# 485Driver_MAX3462.net
KiCad netlist of a schematic drawn in Altium Designer
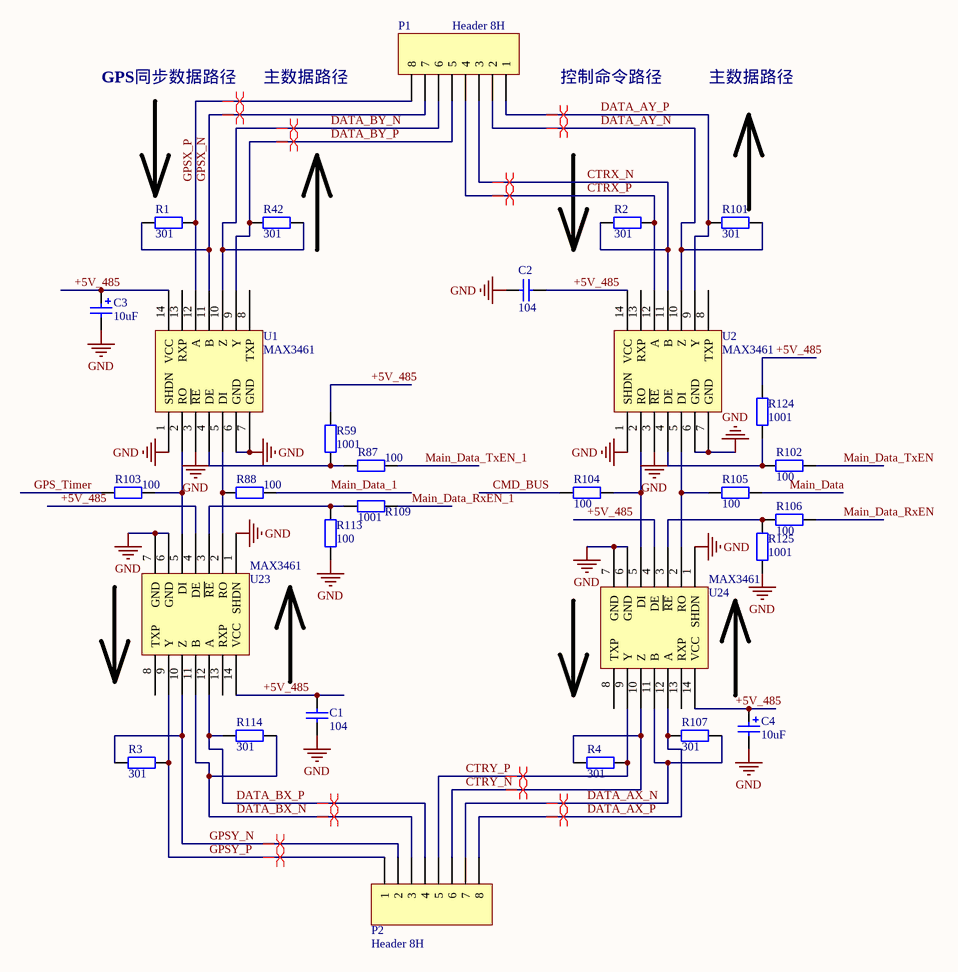
[diagram p0: 485Driver_MAX3462.SchDoc]

(export (version "E")
  (design (tool "Eeschema 10.0.6"))
  (components
    (comp (ref "C1")
      (value "104")
      (footprint "0805C")
      (description "Capacitor")
      (fields (field (name "PUBLISHER") "Altium Limited"))
      (libsource (lib "Miscellaneous Devices") (part "Cap"))
    )
    (comp (ref "C2")
      (value "104")
      (footprint "0805C")
      (description "Capacitor")
      (fields (field (name "PUBLISHER") "Altium Limited"))
      (libsource (lib "Miscellaneous Devices") (part "Cap"))
    )
    (comp (ref "C3")
      (value "10uF")
      (footprint "C68uF")
      (description "Polarized Capacitor (Axial)")
      (fields (field (name "PUBLISHER") "Altium Limited"))
      (libsource (lib "Miscellaneous Devices") (part "Cap Pol2"))
    )
    (comp (ref "C4")
      (value "10uF")
      (footprint "C68uF")
      (description "Polarized Capacitor (Axial)")
      (fields (field (name "PUBLISHER") "Altium Limited"))
      (libsource (lib "Miscellaneous Devices") (part "Cap Pol2"))
    )
    (comp (ref "P1")
      (value "Header 8H")
      (footprint "HDR1X8H")
      (description "Header, 8-Pin, Right Angle")
      (fields (field (name "PUBLISHER") "Altium Limited"))
      (libsource (lib "Miscellaneous Connectors") (part "Header 8H"))
    )
    (comp (ref "P2")
      (value "Header 8H")
      (footprint "HDR1X8H")
      (description "Header, 8-Pin, Right Angle")
      (fields (field (name "PUBLISHER") "Altium Limited"))
      (libsource (lib "") (part "Header 8H_1"))
    )
    (comp (ref "R1")
      (value "301")
      (footprint "0805R")
      (description "Resistor")
      (fields (field (name "PUBLISHER") "Altium Limited"))
      (libsource (lib "Miscellaneous Devices") (part "Res2"))
    )
    (comp (ref "R2")
      (value "301")
      (footprint "0805R")
      (description "Resistor")
      (fields (field (name "PUBLISHER") "Altium Limited"))
      (libsource (lib "Miscellaneous Devices") (part "Res2"))
    )
    (comp (ref "R3")
      (value "301")
      (footprint "0805R")
      (description "Resistor")
      (fields (field (name "PUBLISHER") "Altium Limited"))
      (libsource (lib "Miscellaneous Devices") (part "Res2"))
    )
    (comp (ref "R4")
      (value "301")
      (footprint "0805R")
      (description "Resistor")
      (fields (field (name "PUBLISHER") "Altium Limited"))
      (libsource (lib "Miscellaneous Devices") (part "Res2"))
    )
    (comp (ref "R42")
      (value "301")
      (footprint "0805R")
      (description "Resistor")
      (fields (field (name "PUBLISHER") "Altium Limited"))
      (libsource (lib "Miscellaneous Devices") (part "Res2"))
    )
    (comp (ref "R59")
      (value "1001")
      (footprint "0603")
      (description "Resistor")
      (fields (field (name "PUBLISHER") "Altium Limited"))
      (libsource (lib "") (part "Res2_2"))
    )
    (comp (ref "R87")
      (value "100")
      (footprint "0603")
      (description "Resistor")
      (fields (field (name "PUBLISHER") "Altium Limited"))
      (libsource (lib "Miscellaneous Devices") (part "Res2"))
    )
    (comp (ref "R88")
      (value "100")
      (footprint "0603")
      (description "Resistor")
      (fields (field (name "PUBLISHER") "Altium Limited"))
      (libsource (lib "Miscellaneous Devices") (part "Res2"))
    )
    (comp (ref "R101")
      (value "301")
      (footprint "0805R")
      (description "Resistor")
      (fields (field (name "PUBLISHER") "Altium Limited"))
      (libsource (lib "Miscellaneous Devices") (part "Res2"))
    )
    (comp (ref "R102")
      (value "100")
      (footprint "0603")
      (description "Resistor")
      (fields (field (name "PUBLISHER") "Altium Limited"))
      (libsource (lib "Miscellaneous Devices") (part "Res2"))
    )
    (comp (ref "R103")
      (value "100")
      (footprint "0603")
      (description "Resistor")
      (fields (field (name "PUBLISHER") "Altium Limited"))
      (libsource (lib "Miscellaneous Devices") (part "Res2"))
    )
    (comp (ref "R104")
      (value "100")
      (footprint "0603")
      (description "Resistor")
      (fields (field (name "PUBLISHER") "Altium Limited"))
      (libsource (lib "Miscellaneous Devices") (part "Res2"))
    )
    (comp (ref "R105")
      (value "100")
      (footprint "0603")
      (description "Resistor")
      (fields (field (name "PUBLISHER") "Altium Limited"))
      (libsource (lib "Miscellaneous Devices") (part "Res2"))
    )
    (comp (ref "R106")
      (value "100")
      (footprint "0603")
      (description "Resistor")
      (fields (field (name "PUBLISHER") "Altium Limited"))
      (libsource (lib "Miscellaneous Devices") (part "Res2"))
    )
    (comp (ref "R107")
      (value "301")
      (footprint "0805R")
      (description "Resistor")
      (fields (field (name "PUBLISHER") "Altium Limited"))
      (libsource (lib "Miscellaneous Devices") (part "Res2"))
    )
    (comp (ref "R109")
      (value "1001")
      (footprint "0603")
      (description "Resistor")
      (fields (field (name "PUBLISHER") "Altium Limited"))
      (libsource (lib "") (part "Res2_1"))
    )
    (comp (ref "R113")
      (value "100")
      (footprint "0603")
      (description "Resistor")
      (fields (field (name "PUBLISHER") "Altium Limited"))
      (libsource (lib "") (part "Res2_2"))
    )
    (comp (ref "R114")
      (value "301")
      (footprint "0805R")
      (description "Resistor")
      (fields (field (name "PUBLISHER") "Altium Limited"))
      (libsource (lib "Miscellaneous Devices") (part "Res2"))
    )
    (comp (ref "R124")
      (value "1001")
      (footprint "0603")
      (description "Resistor")
      (fields (field (name "PUBLISHER") "Altium Limited"))
      (libsource (lib "") (part "Res2_2"))
    )
    (comp (ref "R125")
      (value "1001")
      (footprint "0603")
      (description "Resistor")
      (fields (field (name "PUBLISHER") "Altium Limited"))
      (libsource (lib "") (part "Res2_2"))
    )
    (comp (ref "U1") (value "MAX3461") (footprint "SOP14") (libsource (lib "Schlib1") (part "MAX3461")))
    (comp (ref "U2") (value "MAX3461") (footprint "SOP14") (libsource (lib "Schlib1") (part "MAX3461")))
    (comp (ref "U23") (value "MAX3461") (footprint "SOP14") (libsource (lib "") (part "MAX3461_1")))
    (comp (ref "U24") (value "MAX3461") (footprint "SOP14") (libsource (lib "") (part "MAX3461_1")))
  )
  (nets
    (net (code "1") (name "/+5V_485") (class "Default")
      (node (ref "C1") (pin "2") (pinfunction "2_2") (pintype "passive"))
      (node (ref "C2") (pin "2") (pinfunction "2_2") (pintype "passive"))
      (node (ref "C3") (pin "1") (pinfunction "1_1") (pintype "passive"))
      (node (ref "C4") (pin "1") (pinfunction "1_1") (pintype "passive"))
      (node (ref "R124") (pin "1") (pinfunction "1_1") (pintype "passive"))
      (node (ref "R59") (pin "1") (pinfunction "1_1") (pintype "passive"))
      (node (ref "U1") (pin "14") (pinfunction "VCC_14") (pintype "passive"))
      (node (ref "U2") (pin "14") (pinfunction "VCC_14") (pintype "passive"))
      (node (ref "U23") (pin "14") (pinfunction "VCC_14") (pintype "passive"))
      (node (ref "U23") (pin "4") (pinfunction "DE_4") (pintype "passive"))
      (node (ref "U24") (pin "14") (pinfunction "VCC_14") (pintype "passive"))
      (node (ref "U24") (pin "4") (pinfunction "DE_4") (pintype "passive"))
    )
    (net (code "2") (name "/CMD_BUS") (class "Default")
      (node (ref "R104") (pin "2") (pinfunction "2_2") (pintype "passive"))
    )
    (net (code "3") (name "/CTRX_N") (class "Default")
      (node (ref "P1") (pin "3") (pinfunction "3_3") (pintype "passive"))
      (node (ref "R2") (pin "2") (pinfunction "2_2") (pintype "passive"))
      (node (ref "U2") (pin "11") (pinfunction "B_11") (pintype "passive"))
    )
    (net (code "4") (name "/CTRX_P") (class "Default")
      (node (ref "P1") (pin "4") (pinfunction "4_4") (pintype "passive"))
      (node (ref "R2") (pin "1") (pinfunction "1_1") (pintype "passive"))
      (node (ref "U2") (pin "12") (pinfunction "A_12") (pintype "passive"))
    )
    (net (code "5") (name "/CTRY_N") (class "Default")
      (node (ref "P2") (pin "6") (pinfunction "6_6") (pintype "passive"))
      (node (ref "R4") (pin "2") (pinfunction "2_2") (pintype "passive"))
      (node (ref "U24") (pin "10") (pinfunction "Z_10") (pintype "passive"))
    )
    (net (code "6") (name "/CTRY_P") (class "Default")
      (node (ref "P2") (pin "5") (pinfunction "5_5") (pintype "passive"))
      (node (ref "R4") (pin "1") (pinfunction "1_1") (pintype "passive"))
      (node (ref "U24") (pin "9") (pinfunction "Y_9") (pintype "passive"))
    )
    (net (code "7") (name "/DATA_AX_N") (class "Default")
      (node (ref "P2") (pin "7") (pinfunction "7_7") (pintype "passive"))
      (node (ref "R107") (pin "1") (pinfunction "1_1") (pintype "passive"))
      (node (ref "U24") (pin "11") (pinfunction "B_11") (pintype "passive"))
    )
    (net (code "8") (name "/DATA_AX_P") (class "Default")
      (node (ref "P2") (pin "8") (pinfunction "8_8") (pintype "passive"))
      (node (ref "R107") (pin "2") (pinfunction "2_2") (pintype "passive"))
      (node (ref "U24") (pin "12") (pinfunction "A_12") (pintype "passive"))
    )
    (net (code "9") (name "/DATA_AY_N") (class "Default")
      (node (ref "P1") (pin "2") (pinfunction "2_2") (pintype "passive"))
      (node (ref "R101") (pin "1") (pinfunction "1_1") (pintype "passive"))
      (node (ref "U2") (pin "10") (pinfunction "Z_10") (pintype "passive"))
    )
    (net (code "10") (name "/DATA_AY_P") (class "Default")
      (node (ref "P1") (pin "1") (pinfunction "1_1") (pintype "passive"))
      (node (ref "R101") (pin "2") (pinfunction "2_2") (pintype "passive"))
      (node (ref "U2") (pin "9") (pinfunction "Y_9") (pintype "passive"))
    )
    (net (code "11") (name "/DATA_BX_N") (class "Default")
      (node (ref "P2") (pin "3") (pinfunction "3_3") (pintype "passive"))
      (node (ref "R114") (pin "1") (pinfunction "1_1") (pintype "passive"))
      (node (ref "U23") (pin "11") (pinfunction "B_11") (pintype "passive"))
    )
    (net (code "12") (name "/DATA_BX_P") (class "Default")
      (node (ref "P2") (pin "4") (pinfunction "4_4") (pintype "passive"))
      (node (ref "R114") (pin "2") (pinfunction "2_2") (pintype "passive"))
      (node (ref "U23") (pin "12") (pinfunction "A_12") (pintype "passive"))
    )
    (net (code "13") (name "/DATA_BY_N") (class "Default")
      (node (ref "P1") (pin "6") (pinfunction "6_6") (pintype "passive"))
      (node (ref "R42") (pin "1") (pinfunction "1_1") (pintype "passive"))
      (node (ref "U1") (pin "10") (pinfunction "Z_10") (pintype "passive"))
    )
    (net (code "14") (name "/DATA_BY_P") (class "Default")
      (node (ref "P1") (pin "5") (pinfunction "5_5") (pintype "passive"))
      (node (ref "R42") (pin "2") (pinfunction "2_2") (pintype "passive"))
      (node (ref "U1") (pin "9") (pinfunction "Y_9") (pintype "passive"))
    )
    (net (code "15") (name "/GPSX_N") (class "Default")
      (node (ref "P1") (pin "7") (pinfunction "7_7") (pintype "passive"))
      (node (ref "R1") (pin "2") (pinfunction "2_2") (pintype "passive"))
      (node (ref "U1") (pin "11") (pinfunction "B_11") (pintype "passive"))
    )
    (net (code "16") (name "/GPSX_P") (class "Default")
      (node (ref "P1") (pin "8") (pinfunction "8_8") (pintype "passive"))
      (node (ref "R1") (pin "1") (pinfunction "1_1") (pintype "passive"))
      (node (ref "U1") (pin "12") (pinfunction "A_12") (pintype "passive"))
    )
    (net (code "17") (name "/GPSY_N") (class "Default")
      (node (ref "P2") (pin "2") (pinfunction "2_2") (pintype "passive"))
      (node (ref "R3") (pin "2") (pinfunction "2_2") (pintype "passive"))
      (node (ref "U23") (pin "10") (pinfunction "Z_10") (pintype "passive"))
    )
    (net (code "18") (name "/GPSY_P") (class "Default")
      (node (ref "P2") (pin "1") (pinfunction "1_1") (pintype "passive"))
      (node (ref "R3") (pin "1") (pinfunction "1_1") (pintype "passive"))
      (node (ref "U23") (pin "9") (pinfunction "Y_9") (pintype "passive"))
    )
    (net (code "19") (name "/GPS_Timer") (class "Default")
      (node (ref "R103") (pin "2") (pinfunction "2_2") (pintype "passive"))
    )
    (net (code "20") (name "/Main_Data") (class "Default")
      (node (ref "R105") (pin "1") (pinfunction "1_1") (pintype "passive"))
    )
    (net (code "21") (name "/Main_Data_1") (class "Default")
      (node (ref "R88") (pin "1") (pinfunction "1_1") (pintype "passive"))
    )
    (net (code "22") (name "/Main_Data_RxEN") (class "Default")
      (node (ref "R106") (pin "1") (pinfunction "1_1") (pintype "passive"))
    )
    (net (code "23") (name "/Main_Data_RxEN_1") (class "Default")
      (node (ref "R109") (pin "2") (pinfunction "2_2") (pintype "passive"))
    )
    (net (code "24") (name "/Main_Data_TxEN") (class "Default")
      (node (ref "R102") (pin "1") (pinfunction "1_1") (pintype "passive"))
    )
    (net (code "25") (name "/Main_Data_TxEN_1") (class "Default")
      (node (ref "R87") (pin "1") (pinfunction "1_1") (pintype "passive"))
    )
    (net (code "26") (name "GND") (class "Default")
      (node (ref "C1") (pin "1") (pinfunction "1_1") (pintype "passive"))
      (node (ref "C2") (pin "1") (pinfunction "1_1") (pintype "passive"))
      (node (ref "C3") (pin "2") (pinfunction "2_2") (pintype "passive"))
      (node (ref "C4") (pin "2") (pinfunction "2_2") (pintype "passive"))
      (node (ref "R113") (pin "2") (pinfunction "2_2") (pintype "passive"))
      (node (ref "R125") (pin "2") (pinfunction "2_2") (pintype "passive"))
      (node (ref "U1") (pin "1") (pinfunction "SHDN_1") (pintype "passive"))
      (node (ref "U1") (pin "3") (pinfunction "~{RE}_3") (pintype "passive"))
      (node (ref "U1") (pin "6") (pinfunction "GND_6") (pintype "passive"))
      (node (ref "U1") (pin "7") (pinfunction "GND_7") (pintype "passive"))
      (node (ref "U2") (pin "1") (pinfunction "SHDN_1") (pintype "passive"))
      (node (ref "U2") (pin "3") (pinfunction "~{RE}_3") (pintype "passive"))
      (node (ref "U2") (pin "6") (pinfunction "GND_6") (pintype "passive"))
      (node (ref "U2") (pin "7") (pinfunction "GND_7") (pintype "passive"))
      (node (ref "U23") (pin "1") (pinfunction "SHDN_1") (pintype "passive"))
      (node (ref "U23") (pin "6") (pinfunction "GND_6") (pintype "passive"))
      (node (ref "U23") (pin "7") (pinfunction "GND_7") (pintype "passive"))
      (node (ref "U24") (pin "1") (pinfunction "SHDN_1") (pintype "passive"))
      (node (ref "U24") (pin "6") (pinfunction "GND_6") (pintype "passive"))
      (node (ref "U24") (pin "7") (pinfunction "GND_7") (pintype "passive"))
    )
    (net (code "27") (name "Net-(U1-DE)") (class "Default")
      (node (ref "R59") (pin "2") (pinfunction "2_2") (pintype "passive"))
      (node (ref "R87") (pin "2") (pinfunction "2_2") (pintype "passive"))
      (node (ref "U1") (pin "4") (pinfunction "DE_4") (pintype "passive"))
    )
    (net (code "28") (name "Net-(U1-DI)") (class "Default")
      (node (ref "R88") (pin "2") (pinfunction "2_2") (pintype "passive"))
      (node (ref "U1") (pin "5") (pinfunction "DI_5") (pintype "passive"))
      (node (ref "U23") (pin "2") (pinfunction "RO_2") (pintype "passive"))
    )
    (net (code "29") (name "Net-(U1-RO)") (class "Default")
      (node (ref "R103") (pin "1") (pinfunction "1_1") (pintype "passive"))
      (node (ref "U1") (pin "2") (pinfunction "RO_2") (pintype "passive"))
      (node (ref "U23") (pin "5") (pinfunction "DI_5") (pintype "passive"))
    )
    (net (code "30") (name "Net-(U2-DE)") (class "Default")
      (node (ref "R102") (pin "2") (pinfunction "2_2") (pintype "passive"))
      (node (ref "R124") (pin "2") (pinfunction "2_2") (pintype "passive"))
      (node (ref "U2") (pin "4") (pinfunction "DE_4") (pintype "passive"))
    )
    (net (code "31") (name "Net-(U2-DI)") (class "Default")
      (node (ref "R105") (pin "2") (pinfunction "2_2") (pintype "passive"))
      (node (ref "U2") (pin "5") (pinfunction "DI_5") (pintype "passive"))
      (node (ref "U24") (pin "2") (pinfunction "RO_2") (pintype "passive"))
    )
    (net (code "32") (name "Net-(U2-RO)") (class "Default")
      (node (ref "R104") (pin "1") (pinfunction "1_1") (pintype "passive"))
      (node (ref "U2") (pin "2") (pinfunction "RO_2") (pintype "passive"))
      (node (ref "U24") (pin "5") (pinfunction "DI_5") (pintype "passive"))
    )
    (net (code "33") (name "Net-(U23-~{RE})") (class "Default")
      (node (ref "R109") (pin "1") (pinfunction "1_1") (pintype "passive"))
      (node (ref "R113") (pin "1") (pinfunction "1_1") (pintype "passive"))
      (node (ref "U23") (pin "3") (pinfunction "~{RE}_3") (pintype "passive"))
    )
    (net (code "34") (name "Net-(U24-~{RE})") (class "Default")
      (node (ref "R106") (pin "2") (pinfunction "2_2") (pintype "passive"))
      (node (ref "R125") (pin "1") (pinfunction "1_1") (pintype "passive"))
      (node (ref "U24") (pin "3") (pinfunction "~{RE}_3") (pintype "passive"))
    )
    (net (code "35") (name "unconnected-(U1-RXP-Pad13)") (class "Default")
      (node (ref "U1") (pin "13") (pinfunction "RXP_13") (pintype "passive"))
    )
    (net (code "36") (name "unconnected-(U1-TXP-Pad8)") (class "Default")
      (node (ref "U1") (pin "8") (pinfunction "TXP_8") (pintype "passive"))
    )
    (net (code "37") (name "unconnected-(U2-RXP-Pad13)") (class "Default")
      (node (ref "U2") (pin "13") (pinfunction "RXP_13") (pintype "passive"))
    )
    (net (code "38") (name "unconnected-(U2-TXP-Pad8)") (class "Default")
      (node (ref "U2") (pin "8") (pinfunction "TXP_8") (pintype "passive"))
    )
    (net (code "39") (name "unconnected-(U23-RXP-Pad13)") (class "Default")
      (node (ref "U23") (pin "13") (pinfunction "RXP_13") (pintype "passive"))
    )
    (net (code "40") (name "unconnected-(U23-TXP-Pad8)") (class "Default")
      (node (ref "U23") (pin "8") (pinfunction "TXP_8") (pintype "passive"))
    )
    (net (code "41") (name "unconnected-(U24-RXP-Pad13)") (class "Default")
      (node (ref "U24") (pin "13") (pinfunction "RXP_13") (pintype "passive"))
    )
    (net (code "42") (name "unconnected-(U24-TXP-Pad8)") (class "Default")
      (node (ref "U24") (pin "8") (pinfunction "TXP_8") (pintype "passive"))
    )
  )
)
